# Driver.net
KiCad netlist of a schematic drawn in Altium Designer
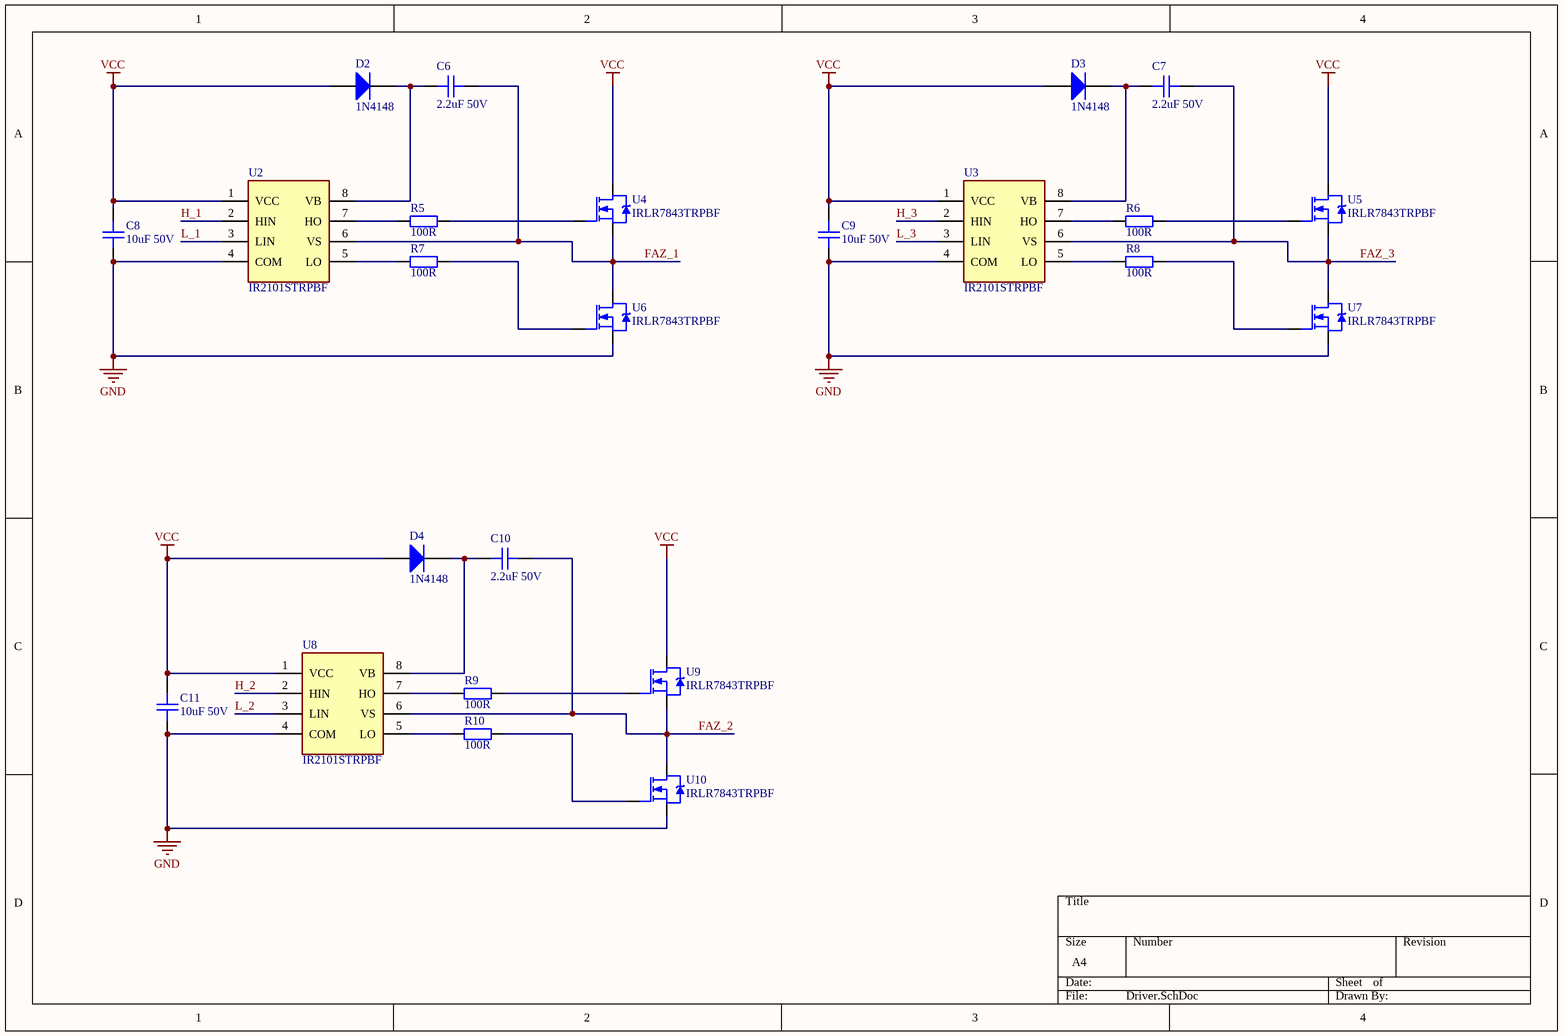
[diagram p0: Driver.SchDoc]

(export (version "E")
  (design (tool "Eeschema 10.0.6"))
  (components
    (comp (ref "C6")
      (value "CAP CER 2.2UF 50V X5R 1206")
      (footprint "CAP 1206/3216")
      (description "2.2µF ±10% 50V Ceramic Capacitor X5R 1206 (3216 Metric)")
      (fields (field (name "DEGER") "2.2uF 50V"))
      (libsource (lib "PROJE") (part "2.2uF 50V 1206"))
    )
    (comp (ref "C7")
      (value "CAP CER 2.2UF 50V X5R 1206")
      (footprint "CAP 1206/3216")
      (description "2.2µF ±10% 50V Ceramic Capacitor X5R 1206 (3216 Metric)")
      (fields (field (name "DEGER") "2.2uF 50V"))
      (libsource (lib "PROJE") (part "2.2uF 50V 1206"))
    )
    (comp (ref "C8")
      (value "CAP CER 10UF 50V X5R 1206")
      (footprint "CAP 1206/3216")
      (description "10µF ±10% 50V Ceramic Capacitor X5R 1206 (3216 Metric)")
      (fields (field (name "DEGER") "10uF 50V"))
      (libsource (lib "PROJE") (part "10uF 50V 1206"))
    )
    (comp (ref "C9")
      (value "CAP CER 10UF 50V X5R 1206")
      (footprint "CAP 1206/3216")
      (description "10µF ±10% 50V Ceramic Capacitor X5R 1206 (3216 Metric)")
      (fields (field (name "DEGER") "10uF 50V"))
      (libsource (lib "PROJE") (part "10uF 50V 1206"))
    )
    (comp (ref "C10")
      (value "CAP CER 2.2UF 50V X5R 1206")
      (footprint "CAP 1206/3216")
      (description "2.2µF ±10% 50V Ceramic Capacitor X5R 1206 (3216 Metric)")
      (fields (field (name "DEGER") "2.2uF 50V"))
      (libsource (lib "PROJE") (part "2.2uF 50V 1206"))
    )
    (comp (ref "C11")
      (value "CAP CER 10UF 50V X5R 1206")
      (footprint "CAP 1206/3216")
      (description "10µF ±10% 50V Ceramic Capacitor X5R 1206 (3216 Metric)")
      (fields (field (name "DEGER") "10uF 50V"))
      (libsource (lib "PROJE") (part "10uF 50V 1206"))
    )
    (comp (ref "D2")
      (value "1N4148 Diyot")
      (footprint "SOD-123")
      (description "DIODE GEN PURP 100V 150MA SOD123")
      (fields (field (name "DEGER") "1N4148"))
      (libsource (lib "PROJE") (part "1N4148"))
    )
    (comp (ref "D3")
      (value "1N4148 Diyot")
      (footprint "SOD-123")
      (description "DIODE GEN PURP 100V 150MA SOD123")
      (fields (field (name "DEGER") "1N4148"))
      (libsource (lib "PROJE") (part "1N4148"))
    )
    (comp (ref "D4")
      (value "1N4148 Diyot")
      (footprint "SOD-123")
      (description "DIODE GEN PURP 100V 150MA SOD123")
      (fields (field (name "DEGER") "1N4148"))
      (libsource (lib "PROJE") (part "1N4148"))
    )
    (comp (ref "R5")
      (value "RES SMD 100 OHM 1% 1/8W 0805")
      (footprint "RES_0805")
      (description "100 Ohms ±1% 0.125W, 1/8W Chip Resistor 0805 (2012 Metric) Moisture Resistant Thick Film")
      (fields (field (name "DEGER") "100R"))
      (libsource (lib "PROJE") (part "100R 0805"))
    )
    (comp (ref "R6")
      (value "RES SMD 100 OHM 1% 1/8W 0805")
      (footprint "RES_0805")
      (description "100 Ohms ±1% 0.125W, 1/8W Chip Resistor 0805 (2012 Metric) Moisture Resistant Thick Film")
      (fields (field (name "DEGER") "100R"))
      (libsource (lib "PROJE") (part "100R 0805"))
    )
    (comp (ref "R7")
      (value "RES SMD 100 OHM 1% 1/8W 0805")
      (footprint "RES_0805")
      (description "100 Ohms ±1% 0.125W, 1/8W Chip Resistor 0805 (2012 Metric) Moisture Resistant Thick Film")
      (fields (field (name "DEGER") "100R"))
      (libsource (lib "PROJE") (part "100R 0805"))
    )
    (comp (ref "R8")
      (value "RES SMD 100 OHM 1% 1/8W 0805")
      (footprint "RES_0805")
      (description "100 Ohms ±1% 0.125W, 1/8W Chip Resistor 0805 (2012 Metric) Moisture Resistant Thick Film")
      (fields (field (name "DEGER") "100R"))
      (libsource (lib "PROJE") (part "100R 0805"))
    )
    (comp (ref "R9")
      (value "RES SMD 100 OHM 1% 1/8W 0805")
      (footprint "RES_0805")
      (description "100 Ohms ±1% 0.125W, 1/8W Chip Resistor 0805 (2012 Metric) Moisture Resistant Thick Film")
      (fields (field (name "DEGER") "100R"))
      (libsource (lib "PROJE") (part "100R 0805"))
    )
    (comp (ref "R10")
      (value "RES SMD 100 OHM 1% 1/8W 0805")
      (footprint "RES_0805")
      (description "100 Ohms ±1% 0.125W, 1/8W Chip Resistor 0805 (2012 Metric) Moisture Resistant Thick Film")
      (fields (field (name "DEGER") "100R"))
      (libsource (lib "PROJE") (part "100R 0805"))
    )
    (comp (ref "U2")
      (value "IC GATE DRVR HALF-BRIDGE 8SOIC")
      (footprint "SOIC8")
      (description "Half-Bridge Gate Driver IC Non-Inverting 8-SOIC")
      (fields (field (name "DEGER") "IR2101STRPBF"))
      (libsource (lib "PROJE") (part "IR2101"))
    )
    (comp (ref "U3")
      (value "IC GATE DRVR HALF-BRIDGE 8SOIC")
      (footprint "SOIC8")
      (description "Half-Bridge Gate Driver IC Non-Inverting 8-SOIC")
      (fields (field (name "DEGER") "IR2101STRPBF"))
      (libsource (lib "PROJE") (part "IR2101"))
    )
    (comp (ref "U4")
      (value "MOSFET N-CH 30V 161A DPAK")
      (footprint "DPAK")
      (description "N-Channel 30V 161A (Tc) 140W (Tc) Surface Mount D-Pak")
      (fields (field (name "DEGER") "IRLR7843TRPBF"))
      (libsource (lib "PROJE") (part "IRLR7843"))
    )
    (comp (ref "U5")
      (value "MOSFET N-CH 30V 161A DPAK")
      (footprint "DPAK")
      (description "N-Channel 30V 161A (Tc) 140W (Tc) Surface Mount D-Pak")
      (fields (field (name "DEGER") "IRLR7843TRPBF"))
      (libsource (lib "PROJE") (part "IRLR7843"))
    )
    (comp (ref "U6")
      (value "MOSFET N-CH 30V 161A DPAK")
      (footprint "DPAK")
      (description "N-Channel 30V 161A (Tc) 140W (Tc) Surface Mount D-Pak")
      (fields (field (name "DEGER") "IRLR7843TRPBF"))
      (libsource (lib "PROJE") (part "IRLR7843"))
    )
    (comp (ref "U7")
      (value "MOSFET N-CH 30V 161A DPAK")
      (footprint "DPAK")
      (description "N-Channel 30V 161A (Tc) 140W (Tc) Surface Mount D-Pak")
      (fields (field (name "DEGER") "IRLR7843TRPBF"))
      (libsource (lib "PROJE") (part "IRLR7843"))
    )
    (comp (ref "U8")
      (value "IC GATE DRVR HALF-BRIDGE 8SOIC")
      (footprint "SOIC8")
      (description "Half-Bridge Gate Driver IC Non-Inverting 8-SOIC")
      (fields (field (name "DEGER") "IR2101STRPBF"))
      (libsource (lib "PROJE") (part "IR2101"))
    )
    (comp (ref "U9")
      (value "MOSFET N-CH 30V 161A DPAK")
      (footprint "DPAK")
      (description "N-Channel 30V 161A (Tc) 140W (Tc) Surface Mount D-Pak")
      (fields (field (name "DEGER") "IRLR7843TRPBF"))
      (libsource (lib "PROJE") (part "IRLR7843"))
    )
    (comp (ref "U10")
      (value "MOSFET N-CH 30V 161A DPAK")
      (footprint "DPAK")
      (description "N-Channel 30V 161A (Tc) 140W (Tc) Surface Mount D-Pak")
      (fields (field (name "DEGER") "IRLR7843TRPBF"))
      (libsource (lib "PROJE") (part "IRLR7843"))
    )
  )
  (nets
    (net (code "1") (name "/FAZ_1") (class "Default")
      (node (ref "C6") (pin "2") (pinfunction "2_2") (pintype "passive"))
      (node (ref "U2") (pin "6") (pinfunction "VS_6") (pintype "passive"))
      (node (ref "U4") (pin "3") (pinfunction "S_3") (pintype "passive"))
      (node (ref "U6") (pin "4") (pinfunction "D_4") (pintype "passive"))
    )
    (net (code "2") (name "/FAZ_2") (class "Default")
      (node (ref "C10") (pin "2") (pinfunction "2_2") (pintype "passive"))
      (node (ref "U10") (pin "4") (pinfunction "D_4") (pintype "passive"))
      (node (ref "U8") (pin "6") (pinfunction "VS_6") (pintype "passive"))
      (node (ref "U9") (pin "3") (pinfunction "S_3") (pintype "passive"))
    )
    (net (code "3") (name "/FAZ_3") (class "Default")
      (node (ref "C7") (pin "2") (pinfunction "2_2") (pintype "passive"))
      (node (ref "U3") (pin "6") (pinfunction "VS_6") (pintype "passive"))
      (node (ref "U5") (pin "3") (pinfunction "S_3") (pintype "passive"))
      (node (ref "U7") (pin "4") (pinfunction "D_4") (pintype "passive"))
    )
    (net (code "4") (name "/H_1") (class "Default")
      (node (ref "U2") (pin "2") (pinfunction "HIN_2") (pintype "passive"))
    )
    (net (code "5") (name "/H_2") (class "Default")
      (node (ref "U8") (pin "2") (pinfunction "HIN_2") (pintype "passive"))
    )
    (net (code "6") (name "/H_3") (class "Default")
      (node (ref "U3") (pin "2") (pinfunction "HIN_2") (pintype "passive"))
    )
    (net (code "7") (name "/L_1") (class "Default")
      (node (ref "U2") (pin "3") (pinfunction "LIN_3") (pintype "passive"))
    )
    (net (code "8") (name "/L_2") (class "Default")
      (node (ref "U8") (pin "3") (pinfunction "LIN_3") (pintype "passive"))
    )
    (net (code "9") (name "/L_3") (class "Default")
      (node (ref "U3") (pin "3") (pinfunction "LIN_3") (pintype "passive"))
    )
    (net (code "10") (name "GND") (class "Default")
      (node (ref "C11") (pin "1") (pinfunction "1_1") (pintype "passive"))
      (node (ref "C8") (pin "1") (pinfunction "1_1") (pintype "passive"))
      (node (ref "C9") (pin "1") (pinfunction "1_1") (pintype "passive"))
      (node (ref "U10") (pin "3") (pinfunction "S_3") (pintype "passive"))
      (node (ref "U2") (pin "4") (pinfunction "COM_4") (pintype "passive"))
      (node (ref "U3") (pin "4") (pinfunction "COM_4") (pintype "passive"))
      (node (ref "U6") (pin "3") (pinfunction "S_3") (pintype "passive"))
      (node (ref "U7") (pin "3") (pinfunction "S_3") (pintype "passive"))
      (node (ref "U8") (pin "4") (pinfunction "COM_4") (pintype "passive"))
    )
    (net (code "11") (name "Net-(D2-K)") (class "Default")
      (node (ref "C6") (pin "1") (pinfunction "1_1") (pintype "passive"))
      (node (ref "D2") (pin "2") (pinfunction "K_2") (pintype "passive"))
      (node (ref "U2") (pin "8") (pinfunction "VB_8") (pintype "passive"))
    )
    (net (code "12") (name "Net-(D3-K)") (class "Default")
      (node (ref "C7") (pin "1") (pinfunction "1_1") (pintype "passive"))
      (node (ref "D3") (pin "2") (pinfunction "K_2") (pintype "passive"))
      (node (ref "U3") (pin "8") (pinfunction "VB_8") (pintype "passive"))
    )
    (net (code "13") (name "Net-(D4-K)") (class "Default")
      (node (ref "C10") (pin "1") (pinfunction "1_1") (pintype "passive"))
      (node (ref "D4") (pin "2") (pinfunction "K_2") (pintype "passive"))
      (node (ref "U8") (pin "8") (pinfunction "VB_8") (pintype "passive"))
    )
    (net (code "14") (name "Net-(U2-HO)") (class "Default")
      (node (ref "R5") (pin "1") (pinfunction "1_1") (pintype "passive"))
      (node (ref "U2") (pin "7") (pinfunction "HO_7") (pintype "passive"))
    )
    (net (code "15") (name "Net-(U2-LO)") (class "Default")
      (node (ref "R7") (pin "1") (pinfunction "1_1") (pintype "passive"))
      (node (ref "U2") (pin "5") (pinfunction "LO_5") (pintype "passive"))
    )
    (net (code "16") (name "Net-(U3-HO)") (class "Default")
      (node (ref "R6") (pin "1") (pinfunction "1_1") (pintype "passive"))
      (node (ref "U3") (pin "7") (pinfunction "HO_7") (pintype "passive"))
    )
    (net (code "17") (name "Net-(U3-LO)") (class "Default")
      (node (ref "R8") (pin "1") (pinfunction "1_1") (pintype "passive"))
      (node (ref "U3") (pin "5") (pinfunction "LO_5") (pintype "passive"))
    )
    (net (code "18") (name "Net-(U4-G)") (class "Default")
      (node (ref "R5") (pin "2") (pinfunction "2_2") (pintype "passive"))
      (node (ref "U4") (pin "1") (pinfunction "G_1") (pintype "passive"))
    )
    (net (code "19") (name "Net-(U5-G)") (class "Default")
      (node (ref "R6") (pin "2") (pinfunction "2_2") (pintype "passive"))
      (node (ref "U5") (pin "1") (pinfunction "G_1") (pintype "passive"))
    )
    (net (code "20") (name "Net-(U6-G)") (class "Default")
      (node (ref "R7") (pin "2") (pinfunction "2_2") (pintype "passive"))
      (node (ref "U6") (pin "1") (pinfunction "G_1") (pintype "passive"))
    )
    (net (code "21") (name "Net-(U7-G)") (class "Default")
      (node (ref "R8") (pin "2") (pinfunction "2_2") (pintype "passive"))
      (node (ref "U7") (pin "1") (pinfunction "G_1") (pintype "passive"))
    )
    (net (code "22") (name "Net-(U8-HO)") (class "Default")
      (node (ref "R9") (pin "1") (pinfunction "1_1") (pintype "passive"))
      (node (ref "U8") (pin "7") (pinfunction "HO_7") (pintype "passive"))
    )
    (net (code "23") (name "Net-(U8-LO)") (class "Default")
      (node (ref "R10") (pin "1") (pinfunction "1_1") (pintype "passive"))
      (node (ref "U8") (pin "5") (pinfunction "LO_5") (pintype "passive"))
    )
    (net (code "24") (name "Net-(U9-G)") (class "Default")
      (node (ref "R9") (pin "2") (pinfunction "2_2") (pintype "passive"))
      (node (ref "U9") (pin "1") (pinfunction "G_1") (pintype "passive"))
    )
    (net (code "25") (name "Net-(U10-G)") (class "Default")
      (node (ref "R10") (pin "2") (pinfunction "2_2") (pintype "passive"))
      (node (ref "U10") (pin "1") (pinfunction "G_1") (pintype "passive"))
    )
    (net (code "26") (name "VCC") (class "Default")
      (node (ref "C11") (pin "2") (pinfunction "2_2") (pintype "passive"))
      (node (ref "C8") (pin "2") (pinfunction "2_2") (pintype "passive"))
      (node (ref "C9") (pin "2") (pinfunction "2_2") (pintype "passive"))
      (node (ref "D2") (pin "1") (pinfunction "A_1") (pintype "passive"))
      (node (ref "D3") (pin "1") (pinfunction "A_1") (pintype "passive"))
      (node (ref "D4") (pin "1") (pinfunction "A_1") (pintype "passive"))
      (node (ref "U2") (pin "1") (pinfunction "VCC_1") (pintype "passive"))
      (node (ref "U3") (pin "1") (pinfunction "VCC_1") (pintype "passive"))
      (node (ref "U4") (pin "4") (pinfunction "D_4") (pintype "passive"))
      (node (ref "U5") (pin "4") (pinfunction "D_4") (pintype "passive"))
      (node (ref "U8") (pin "1") (pinfunction "VCC_1") (pintype "passive"))
      (node (ref "U9") (pin "4") (pinfunction "D_4") (pintype "passive"))
    )
  )
)
